# Hedgehog.net
KiCad netlist of a schematic drawn in Altium Designer
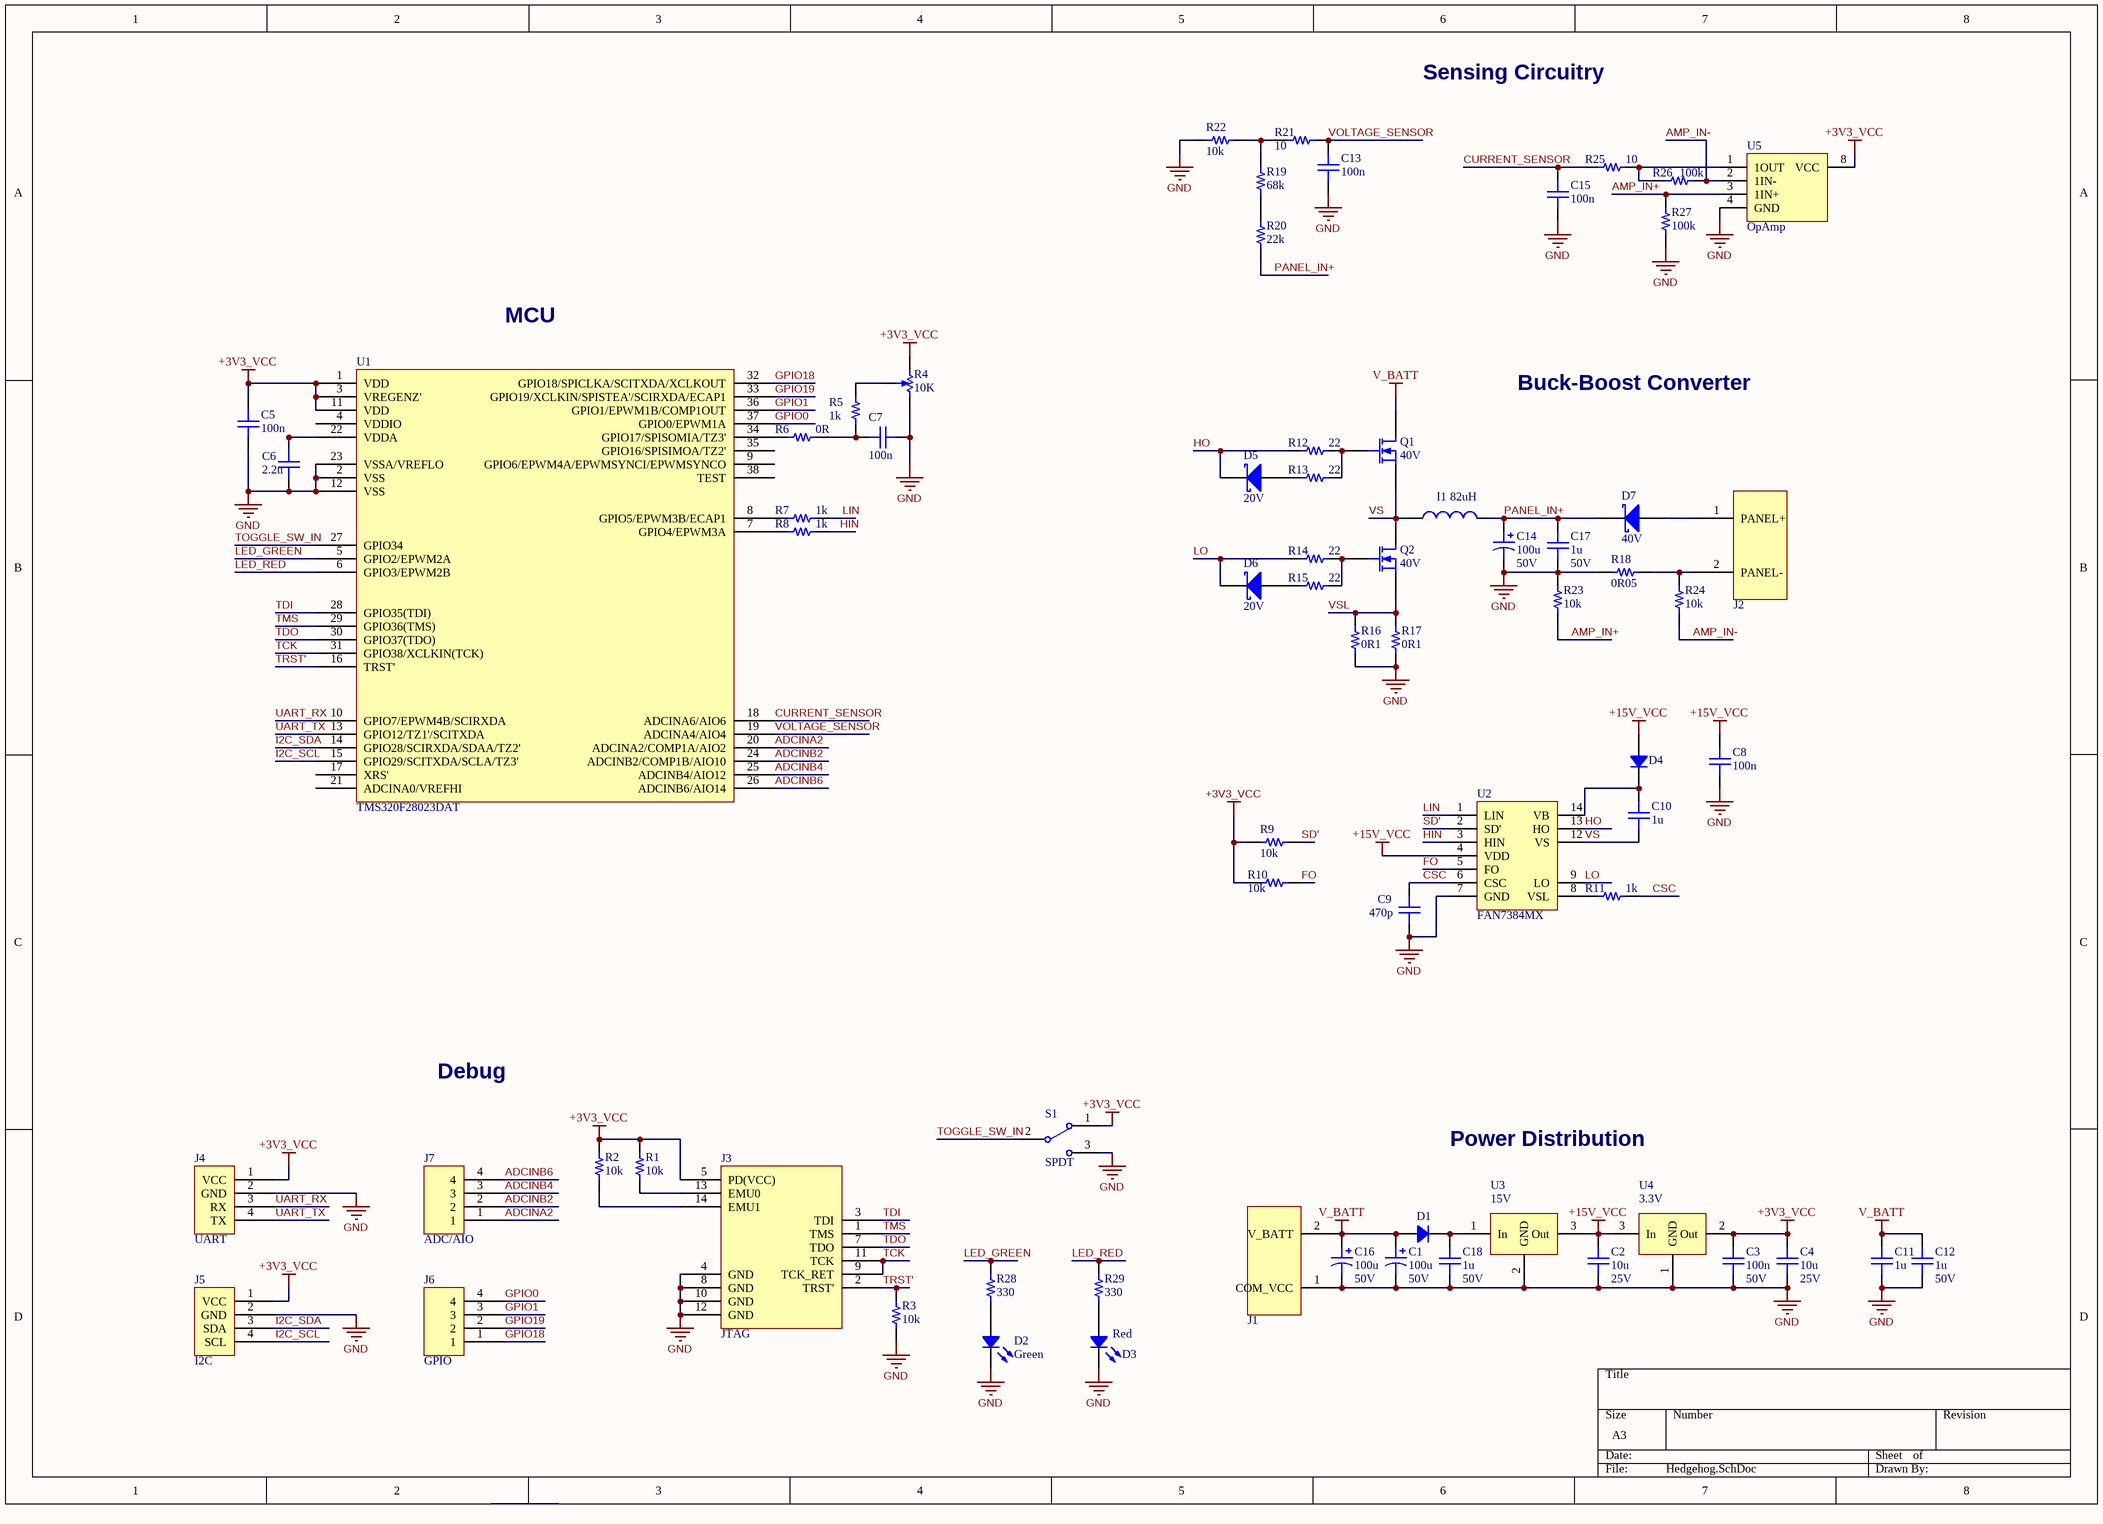
[diagram p0: Hedgehog.SchDoc]

(export (version "E")
  (design (tool "Eeschema 10.0.6"))
  (components
    (comp (ref "C1")
      (value "100u")
      (footprint "CAP-100uF-50V-20%-THM-Radial Panasonic Electronic Components")
      (description "Polarized Capacitor, 100uF, 50V Voltage Rating, Through Hole Radial Package")
      (fields (field (name "VOLTAGERATING") "50V"))
      (libsource (lib "PwrSupply-Schematics-Library") (part "100u-50V-THM-Radial-20%"))
    )
    (comp (ref "C2")
      (value "10u")
      (footprint "CAP 1206/3216 Murata")
      (description "Capacitor, 10uF, 25V Voltage Rating, 1206 Package")
      (fields (field (name "VOLTAGERATING") "25V"))
      (libsource (lib "Capacitor SMD") (part "10u-25V-1206-10%"))
    )
    (comp (ref "C3")
      (value "100n")
      (footprint "CAP 0805/2012")
      (description "Capacitor, 100nF, 50V Voltage Rating, 0805 Package")
      (fields (field (name "VOLTAGERATING") "50V"))
      (libsource (lib "Capacitor SMD") (part "100n-50V-0805-10%"))
    )
    (comp (ref "C4")
      (value "10u")
      (footprint "CAP 1206/3216 Murata")
      (description "Capacitor, 10uF, 25V Voltage Rating, 1206 Package")
      (fields (field (name "VOLTAGERATING") "25V"))
      (libsource (lib "Capacitor SMD") (part "10u-25V-1206-10%"))
    )
    (comp (ref "C5")
      (value "100n")
      (footprint "CAP 0805/2012")
      (description "Capacitor, 100nF, 50V Voltage Rating, 0805 Package")
      (libsource (lib "Capacitor SMD") (part "100n-50V-0805-10%"))
    )
    (comp (ref "C6")
      (value "2.2u")
      (footprint "CAP 0805/2012")
      (description "Capacitor, 2.2uF, 25V Voltage Rating, 0805 Package")
      (libsource (lib "Capacitor SMD") (part "2.2u-25V-0805-10%"))
    )
    (comp (ref "C7")
      (value "100n")
      (footprint "CAP 0805/2012")
      (description "Capacitor, 100nF, 50V Voltage Rating, 0805 Package")
      (libsource (lib "Capacitor SMD") (part "100n-50V-0805-10%"))
    )
    (comp (ref "C8")
      (value "100n")
      (footprint "CAP 0805/2012")
      (description "Capacitor, 100nF, 50V Voltage Rating, 0805 Package")
      (libsource (lib "Capacitor SMD") (part "100n-50V-0805-10%"))
    )
    (comp (ref "C9")
      (value "470p")
      (footprint "CAP 0805/2012")
      (description "Capacitor, 470pF, 50V Voltage Rating, 0805 Package")
      (libsource (lib "Capacitor SMD") (part "470p-50V-0805-5%"))
    )
    (comp (ref "C10")
      (value "1u")
      (footprint "CAP 0805/2012")
      (description "Capacitor,1uF, 25V Voltage Rating, 0805 Package")
      (libsource (lib "Capacitor SMD") (part "1u-25V-0805-10%"))
    )
    (comp (ref "C11")
      (value "1u")
      (footprint "CAP-TH-Radial_1uF-Non_Polarised-KEMET")
      (description "Capacitor, 1uF, 63V Voltage Rating, RADIAL Package")
      (libsource (lib "PwrSupply-Schematics-Library") (part "1u-63V-THM-Radial-10%"))
    )
    (comp (ref "C12")
      (value "1u")
      (footprint "CAP 1206/3216 Murata")
      (description "Capacitor, 1uF, 50V Voltage Rating, 1206 Package")
      (fields (field (name "VOLTAGERATING") "50V"))
      (libsource (lib "Capacitor SMD") (part "1u-50V-1206-10%"))
    )
    (comp (ref "C13")
      (value "100n")
      (footprint "CAP 0805/2012")
      (description "Capacitor, 100nF, 50V Voltage Rating, 0805 Package")
      (libsource (lib "Capacitor SMD") (part "100n-50V-0805-10%"))
    )
    (comp (ref "C14")
      (value "100u")
      (footprint "CAP-100uF-50V-20%-THM-Radial Panasonic Electronic Components")
      (description "Polarized Capacitor, 100uF, 50V Voltage Rating, Through Hole Radial Package")
      (fields (field (name "VOLTAGERATING") "50V"))
      (libsource (lib "PwrSupply-Schematics-Library") (part "100u-50V-THM-Radial-20%"))
    )
    (comp (ref "C15")
      (value "100n")
      (footprint "CAP 0805/2012")
      (description "Capacitor, 100nF, 50V Voltage Rating, 0805 Package")
      (libsource (lib "Capacitor SMD") (part "100n-50V-0805-10%"))
    )
    (comp (ref "C16")
      (value "100u")
      (footprint "CAP-100uF-50V-20%-THM-Radial Panasonic Electronic Components")
      (description "Polarized Capacitor, 100uF, 50V Voltage Rating, Through Hole Radial Package")
      (fields (field (name "VOLTAGERATING") "50V"))
      (libsource (lib "PwrSupply-Schematics-Library") (part "100u-50V-THM-Radial-20%"))
    )
    (comp (ref "C17")
      (value "1u")
      (footprint "CAP 1206/3216 Murata")
      (description "Capacitor, 1uF, 50V Voltage Rating, 1206 Package")
      (fields (field (name "VOLTAGERATING") "50V"))
      (libsource (lib "Capacitor SMD") (part "1u-50V-1206-10%"))
    )
    (comp (ref "C18")
      (value "1u")
      (footprint "CAP 1206/3216 Murata")
      (description "Capacitor, 1uF, 50V Voltage Rating, 1206 Package")
      (fields (field (name "VOLTAGERATING") "50V"))
      (libsource (lib "Capacitor SMD") (part "1u-50V-1206-10%"))
    )
    (comp (ref "D1")
      (value "400V-1A-GenPurp-SMA")
      (footprint "SMA Diodes Incorporated")
      (description "Diode, 400V Voltage Rating, 1A Current Rating, General Purpose Type, SMA Package")
      (fields (field (name "MANUFACTURER") "ON Semiconductor"))
      (libsource (lib "Diode SMD") (part "400V-1A-GenPurp-SMA"))
    )
    (comp (ref "D2")
      (value "LED-Green-1206")
      (footprint "LED 1206/3216 Kingbright")
      (description "LED, Green Color, 1206 Package")
      (fields (field (name "MANUFACTURER") "Kingbright") (field (name "COLOR") "Green"))
      (libsource (lib "Diode SMD") (part "LED-Green-1206"))
    )
    (comp (ref "D3")
      (value "LED-Red-1206")
      (footprint "LED 1206/3216 Kingbright")
      (description "LED, Red Color, 1206 Package")
      (fields (field (name "MANUFACTURER") "Kingbright") (field (name "COLOR") "Red"))
      (libsource (lib "Diode SMD") (part "LED-Red-1206"))
    )
    (comp (ref "D4")
      (value "400V-2A-Fast-SMA")
      (footprint "SMA Diodes Incorporated")
      (description "Diode, 400V Voltage Rating, 2A Current Rating, Fast Type, SMA Package")
      (fields (field (name "MANUFACTURER") "ON Semiconductor"))
      (libsource (lib "Diode SMD") (part "400V-2A-Fast-SMA"))
    )
    (comp (ref "D5")
      (value "20V-1A-SCHOTTKY-SOD123W")
      (footprint "CFP3-SOD123W-Nexperia USA Inc.")
      (description "Diode, 20V Voltage Rating, 1A Current Rating, SCHOTTKY Type, SOD123W Package")
      (fields (field (name "MANUFACTURER") "Nexperia USA Inc.") (field (name "VOLTAGERATING") "20V"))
      (libsource (lib "PwrSupply-Schematics-Library") (part "20V-1A-SCHOTTKY-SOD123W"))
    )
    (comp (ref "D6")
      (value "20V-1A-SCHOTTKY-SOD123W")
      (footprint "CFP3-SOD123W-Nexperia USA Inc.")
      (description "Diode, 20V Voltage Rating, 1A Current Rating, SCHOTTKY Type, SOD123W Package")
      (fields (field (name "MANUFACTURER") "Nexperia USA Inc.") (field (name "VOLTAGERATING") "20V"))
      (libsource (lib "PwrSupply-Schematics-Library") (part "20V-1A-SCHOTTKY-SOD123W"))
    )
    (comp (ref "D7")
      (value "40V-5A-SCHOTTKY-SMC")
      (footprint "DIOM6959X25L")
      (description "Diode, 40V Voltage Rating, 5A Current Rating, SCHOTTKY Type, SMC Package")
      (fields (field (name "MANUFACTURER") "Diodes Incorporated") (field (name "VOLTAGERATING") "40V"))
      (libsource (lib "PwrSupply-Schematics-Library") (part "40V-5A-SCHOTTKY-SMC"))
    )
    (comp (ref "I1")
      (value "82uH")
      (footprint "Inductor-82uH-Pulse Electronics Power")
      (description "82u, 6.5A Current Rating, 83mOhm Resistance, ThroughHole Package")
      (libsource (lib "PwrSupply-Schematics-Library") (part "82uH-6.5A-83mOhm"))
    )
    (comp (ref "J1")
      (value "~")
      (footprint "TWO_PIN_CONNECTOR-15A-On Shore Technology Inc.")
      (description "Slide Toggle Switch, 300V Voltage Rating, 15A Current Rating,")
      (fields (field (name "MANUFACTURER") "On Shore Technology Inc."))
      (libsource (lib "PwrSupply-Schematics-Library") (part "TwoPin-Connector-15A-300V-THM"))
    )
    (comp (ref "J2")
      (value "~")
      (footprint "TWO_PIN_CONNECTOR-15A-On Shore Technology Inc.")
      (description "Slide Toggle Switch, 300V Voltage Rating, 15A Current Rating,")
      (fields (field (name "MANUFACTURER") "On Shore Technology Inc."))
      (libsource (lib "") (part "TwoPin-Connector-15A-300V-THM_1"))
    )
    (comp (ref "J3")
      (value "JTAG")
      (footprint "14Pin-Connector-2.54mmx2.54mmPitch On Shore Technology Inc.")
      (description "14Pin-Connector")
      (fields (field (name "MANUFACTURER") "On Shore Technology Inc."))
      (libsource (lib "PwrSupply-Schematics-Library") (part "14Pin-Connector"))
    )
    (comp (ref "J4")
      (value "I2C")
      (footprint "4Pin_Connector-Wurth Electronics Inc.")
      (description "4Pin-Connector")
      (libsource (lib "PwrSupply-Schematics-Library") (part "4Pin-Connector"))
    )
    (comp (ref "J5")
      (value "UART")
      (footprint "4Pin_Connector-Wurth Electronics Inc.")
      (description "4Pin-Connector")
      (libsource (lib "PwrSupply-Schematics-Library") (part "4Pin-Connector"))
    )
    (comp (ref "J6")
      (value "GPIO")
      (footprint "4Pin_Connector-Wurth Electronics Inc.")
      (description "4Pin-Connector")
      (libsource (lib "") (part "4Pin-Connector_1"))
    )
    (comp (ref "J7")
      (value "ADC/AIO")
      (footprint "4Pin_Connector-Wurth Electronics Inc.")
      (description "4Pin-Connector")
      (libsource (lib "") (part "4Pin-Connector_1"))
    )
    (comp (ref "Q1")
      (value "40V")
      (footprint "DPAK/TO252-3-5.46mmWidth(Tab) ON Semiconductor - VIAS")
      (description "N-CH, 40V Voltage Rating, 6A Current Rating,  1.71W Power Rating, DPAK Package")
      (libsource (lib "PwrSupply-Schematics-Library") (part "Mosfet-40V-6A-1.71W-SMD-DPAK"))
    )
    (comp (ref "Q2")
      (value "40V")
      (footprint "DPAK/TO252-3-5.46mmWidth(Tab) ON Semiconductor - VIAS")
      (description "N-CH, 40V Voltage Rating, 6A Current Rating,  1.71W Power Rating, DPAK Package")
      (libsource (lib "PwrSupply-Schematics-Library") (part "Mosfet-40V-6A-1.71W-SMD-DPAK"))
    )
    (comp (ref "R1")
      (value "10k")
      (footprint "RES 0805/2012")
      (description "Resistor, 10k, 125mW Power Rating, 0805 Package")
      (libsource (lib "Resistor SMD") (part "10k-125mW-0805-1%"))
    )
    (comp (ref "R2")
      (value "10k")
      (footprint "RES 0805/2012")
      (description "Resistor, 10k, 125mW Power Rating, 0805 Package")
      (libsource (lib "Resistor SMD") (part "10k-125mW-0805-1%"))
    )
    (comp (ref "R3")
      (value "10k")
      (footprint "RES 0805/2012")
      (description "Resistor, 10k, 125mW Power Rating, 0805 Package")
      (libsource (lib "Resistor SMD") (part "10k-125mW-0805-1%"))
    )
    (comp (ref "R4")
      (value "10K")
      (footprint "Potentiometer-TC33X-2-103E-Bourns Inc.")
      (description "Potentiometer, 10kOhm Resistance, Current Rating, 0.1W Power Rating")
      (fields (field (name "MANUFACTURER") "Bourns Inc."))
      (libsource (lib "PwrSupply-Schematics-Library") (part "Pot-10kOhm-0.1W-20%"))
    )
    (comp (ref "R5")
      (value "1k")
      (footprint "RES 0805/2012")
      (description "Resistor, 1k, 125mW Power Rating, 0805 Package")
      (libsource (lib "Resistor SMD") (part "1k-125mW-0805-1%"))
    )
    (comp (ref "R6")
      (value "0R")
      (footprint "RES 0805/2012")
      (description "Resistor, 0 , 125mW Power Rating, 0805 Package")
      (libsource (lib "Resistor SMD") (part "0k-125mW-0805-Jumper"))
    )
    (comp (ref "R7")
      (value "1k")
      (footprint "RES 0805/2012")
      (description "Resistor, 1k, 125mW Power Rating, 0805 Package")
      (libsource (lib "Resistor SMD") (part "1k-125mW-0805-1%"))
    )
    (comp (ref "R8")
      (value "1k")
      (footprint "RES 0805/2012")
      (description "Resistor, 1k, 125mW Power Rating, 0805 Package")
      (libsource (lib "Resistor SMD") (part "1k-125mW-0805-1%"))
    )
    (comp (ref "R9")
      (value "10k")
      (footprint "RES 0805/2012")
      (description "Resistor, 10k, 125mW Power Rating, 0805 Package")
      (libsource (lib "Resistor SMD") (part "10k-125mW-0805-1%"))
    )
    (comp (ref "R10")
      (value "10k")
      (footprint "RES 0805/2012")
      (description "Resistor, 10k, 125mW Power Rating, 0805 Package")
      (libsource (lib "Resistor SMD") (part "10k-125mW-0805-1%"))
    )
    (comp (ref "R11")
      (value "1k")
      (footprint "RES 0805/2012")
      (description "Resistor, 1k, 125mW Power Rating, 0805 Package")
      (libsource (lib "Resistor SMD") (part "1k-125mW-0805-1%"))
    )
    (comp (ref "R12")
      (value "22")
      (footprint "RES 0805/2012")
      (description "Resistor, 22, 125mW Power Rating, 0805 Package")
      (libsource (lib "Resistor SMD") (part "22-125mW-0805-1%"))
    )
    (comp (ref "R13")
      (value "22")
      (footprint "RES 0805/2012")
      (description "Resistor, 22, 125mW Power Rating, 0805 Package")
      (libsource (lib "Resistor SMD") (part "22-125mW-0805-1%"))
    )
    (comp (ref "R14")
      (value "22")
      (footprint "RES 0805/2012")
      (description "Resistor, 22, 125mW Power Rating, 0805 Package")
      (libsource (lib "Resistor SMD") (part "22-125mW-0805-1%"))
    )
    (comp (ref "R15")
      (value "22")
      (footprint "RES 0805/2012")
      (description "Resistor, 22, 125mW Power Rating, 0805 Package")
      (libsource (lib "Resistor SMD") (part "22-125mW-0805-1%"))
    )
    (comp (ref "R16")
      (value "0R1")
      (footprint "RES 2512/6432")
      (description "Resistor, 0.1 Ohm, 1W Power Rating, 2010 Package")
      (libsource (lib "PwrSupply-Schematics-Library") (part "RES-0.1-1W-SMD-2010-1%"))
    )
    (comp (ref "R17")
      (value "0R1")
      (footprint "RES 2512/6432")
      (description "Resistor, 0.1 Ohm, 1W Power Rating, 2010 Package")
      (libsource (lib "PwrSupply-Schematics-Library") (part "RES-0.1-1W-SMD-2010-1%"))
    )
    (comp (ref "R18")
      (value "0R05")
      (footprint "RES 2512/6432")
      (description "Resistor, 0.05 Ohm, 3W Power Rating, 2512 Package")
      (libsource (lib "PwrSupply-Schematics-Library") (part "RES-0.05-3W-SMD-2512-1%"))
    )
    (comp (ref "R19")
      (value "68k")
      (footprint "RES 0805/2012")
      (description "Resistor, 68k, 125mW Power Rating, Package")
      (libsource (lib "Resistor SMD") (part "68k-125mW-0805-1%"))
    )
    (comp (ref "R20")
      (value "22k")
      (footprint "RES 0805/2012")
      (description "Resistor, 22k, 125mW Power Rating, 0805 Package")
      (libsource (lib "Resistor SMD") (part "22k-125mW-0805-1%"))
    )
    (comp (ref "R21")
      (value "10")
      (footprint "RES 0805/2012")
      (description "Resistor, 10, 125mW Power Rating, 0805 Package")
      (libsource (lib "Resistor SMD") (part "10-125mW-0805-1%"))
    )
    (comp (ref "R22")
      (value "10k")
      (footprint "RES 0805/2012")
      (description "Resistor, 10k, 125mW Power Rating, 0805 Package")
      (libsource (lib "Resistor SMD") (part "10k-125mW-0805-1%"))
    )
    (comp (ref "R23")
      (value "10k")
      (footprint "RES 0805/2012")
      (description "Resistor, 10k, 125mW Power Rating, 0805 Package")
      (libsource (lib "Resistor SMD") (part "10k-125mW-0805-1%"))
    )
    (comp (ref "R24")
      (value "10k")
      (footprint "RES 0805/2012")
      (description "Resistor, 10k, 125mW Power Rating, 0805 Package")
      (libsource (lib "Resistor SMD") (part "10k-125mW-0805-1%"))
    )
    (comp (ref "R25")
      (value "10")
      (footprint "RES 0805/2012")
      (description "Resistor, 10, 125mW Power Rating, 0805 Package")
      (libsource (lib "Resistor SMD") (part "10-125mW-0805-1%"))
    )
    (comp (ref "R26")
      (value "100k")
      (footprint "RES 0805/2012")
      (description "Resistor, 100k, 125mW Power Rating, 0805 Package")
      (libsource (lib "Resistor SMD") (part "100k-125mW-0805-1%"))
    )
    (comp (ref "R27")
      (value "100k")
      (footprint "RES 0805/2012")
      (description "Resistor, 100k, 125mW Power Rating, 0805 Package")
      (libsource (lib "Resistor SMD") (part "100k-125mW-0805-1%"))
    )
    (comp (ref "R28")
      (value "330")
      (footprint "RES 0805/2012")
      (description "Resistor, 330, 125mW Power Rating, 0805 Package")
      (libsource (lib "Resistor SMD") (part "330-125mW-0805-1%"))
    )
    (comp (ref "R29")
      (value "330")
      (footprint "RES 0805/2012")
      (description "Resistor, 330, 125mW Power Rating, 0805 Package")
      (libsource (lib "Resistor SMD") (part "330-125mW-0805-1%"))
    )
    (comp (ref "S1")
      (value "SPDT")
      (footprint "Toggle_Switch-SPDT-C&K")
      (description "Slide Toggle Switch, 12V Voltage Rating, 100mA Current Rating, Through Hole Package")
      (fields (field (name "MANUFACTURER") "C&K"))
      (libsource (lib "PwrSupply-Schematics-Library") (part "ToggleSwitch-SPDT-12V-100mA"))
    )
    (comp (ref "U1")
      (value "TMS320F28023DAT")
      (description "IC MCU 32BIT 64KB FLASH 38TSSOP")
      (fields (field (name "MANUFACTURER") "Texas Instruments"))
      (libsource (lib "PwrSupply-Schematics-Library") (part "MC-TMS320F28023DAT_Modified"))
    )
    (comp (ref "U2")
      (value "FAN7384MX")
      (footprint "14SOIC-3.9mmWidth ON Semiconductor")
      (description "Half-Bridge Gate Driver IC Non-Inverting 14-SOIC")
      (fields (field (name "MANUFACTURER") "ON Semiconductor"))
      (libsource (lib "IC Driver") (part "FAN7384MX"))
    )
    (comp (ref "U3")
      (value "15V")
      (footprint "DPAK/TO252-3-5.46mmWidth(Tab) ON Semiconductor")
      (description "Voltage Regulator, 15V OutputVoltage, 1A MaxCurrent, LDO Type, DPAK Package")
      (fields (field (name "MANUFACTURER") "ON Semiconductor") (field (name "OUTPUTVOLTAGE") "15V"))
      (libsource (lib "PwrSupply-Schematics-Library") (part "15V-1A-LDO-SMD-DPAK"))
    )
    (comp (ref "U4")
      (value "Voltage Regulator")
      (footprint "SOT223/TO261-4 Diodes Incorporated")
      (description "Voltage Regulator, 3.3V OutputVoltage, 1A MaxCurrent, LDO Type, SOT223 Package")
      (fields (field (name "MANUFACTURER") "Diodes Incorporated") (field (name "OUTPUTVOLTAGE") "3.3V"))
      (libsource (lib "IC Regulator") (part "3.3V-1A-LDO-SMD-SOT223_2"))
    )
    (comp (ref "U5")
      (value "OpAmp")
      (footprint "8SOIC-3.9mmWidth")
      (description "IC OPAMP GP 700KHZ 8SOIC")
      (fields (field (name "MANUFACTURER") "Texas Instruments"))
      (libsource (lib "IC OpAmp") (part "LM358AD"))
    )
  )
  (nets
    (net (code "1") (name "+3V3_VCC") (class "Default")
      (node (ref "C3") (pin "2") (pinfunction "2_2") (pintype "passive"))
      (node (ref "C4") (pin "1") (pinfunction "1_1") (pintype "passive"))
      (node (ref "C5") (pin "2") (pinfunction "2_2") (pintype "passive"))
      (node (ref "J3") (pin "5") (pinfunction "PD(VCC)_5") (pintype "passive"))
      (node (ref "J4") (pin "1") (pinfunction "VCC_1") (pintype "passive"))
      (node (ref "J5") (pin "1") (pinfunction "VCC_1") (pintype "passive"))
      (node (ref "R1") (pin "2") (pinfunction "2_2") (pintype "passive"))
      (node (ref "R10") (pin "1") (pinfunction "1_1") (pintype "passive"))
      (node (ref "R2") (pin "2") (pinfunction "2_2") (pintype "passive"))
      (node (ref "R4") (pin "3") (pinfunction "CW_3") (pintype "passive"))
      (node (ref "R9") (pin "1") (pinfunction "1_1") (pintype "passive"))
      (node (ref "S1") (pin "1") (pinfunction "3_1") (pintype "passive"))
      (node (ref "U1") (pin "1") (pinfunction "VDD_1") (pintype "passive"))
      (node (ref "U1") (pin "11") (pinfunction "VDD_11") (pintype "passive"))
      (node (ref "U1") (pin "3") (pinfunction "VREGENZ'_3") (pintype "passive"))
      (node (ref "U4") (pin "2") (pinfunction "Out_2") (pintype "passive"))
      (node (ref "U5") (pin "8") (pinfunction "VCC_8") (pintype "passive"))
    )
    (net (code "2") (name "+15V_VCC") (class "Default")
      (node (ref "C2") (pin "1") (pinfunction "1_1") (pintype "passive"))
      (node (ref "C8") (pin "1") (pinfunction "1_1") (pintype "passive"))
      (node (ref "D4") (pin "1") (pinfunction "1_1") (pintype "passive"))
      (node (ref "U2") (pin "4") (pinfunction "VDD_4") (pintype "passive"))
      (node (ref "U3") (pin "3") (pinfunction "Out_3") (pintype "passive"))
      (node (ref "U4") (pin "3") (pinfunction "In_3") (pintype "passive"))
    )
    (net (code "3") (name "/ADCINA2") (class "Default")
      (node (ref "J7") (pin "1") (pinfunction "1_1") (pintype "passive"))
      (node (ref "U1") (pin "20") (pinfunction "ADCINA2/COMP1A/AIO2_20") (pintype "passive"))
    )
    (net (code "4") (name "/ADCINB2") (class "Default")
      (node (ref "J7") (pin "2") (pinfunction "2_2") (pintype "passive"))
      (node (ref "U1") (pin "24") (pinfunction "ADCINB2/COMP1B/AIO10_24") (pintype "passive"))
    )
    (net (code "5") (name "/ADCINB4") (class "Default")
      (node (ref "J7") (pin "3") (pinfunction "3_3") (pintype "passive"))
      (node (ref "U1") (pin "25") (pinfunction "ADCINB4/AIO12_25") (pintype "passive"))
    )
    (net (code "6") (name "/ADCINB6") (class "Default")
      (node (ref "J7") (pin "4") (pinfunction "4_4") (pintype "passive"))
      (node (ref "U1") (pin "26") (pinfunction "ADCINB6/AIO14_26") (pintype "passive"))
    )
    (net (code "7") (name "/AMP_IN+") (class "Default")
      (node (ref "R23") (pin "1") (pinfunction "1_1") (pintype "passive"))
      (node (ref "R27") (pin "1") (pinfunction "1_1") (pintype "passive"))
      (node (ref "U5") (pin "3") (pinfunction "1IN+_3") (pintype "passive"))
    )
    (net (code "8") (name "/AMP_IN-") (class "Default")
      (node (ref "R24") (pin "1") (pinfunction "1_1") (pintype "passive"))
      (node (ref "R26") (pin "2") (pinfunction "2_2") (pintype "passive"))
      (node (ref "U5") (pin "2") (pinfunction "1IN-_2") (pintype "passive"))
    )
    (net (code "9") (name "/CSC") (class "Default")
      (node (ref "C9") (pin "2") (pinfunction "2_2") (pintype "passive"))
      (node (ref "R11") (pin "1") (pinfunction "1_1") (pintype "passive"))
      (node (ref "U2") (pin "6") (pinfunction "CSC_6") (pintype "passive"))
    )
    (net (code "10") (name "/CURRENT_SENSOR") (class "Default")
      (node (ref "C15") (pin "1") (pinfunction "1_1") (pintype "passive"))
      (node (ref "R25") (pin "2") (pinfunction "2_2") (pintype "passive"))
      (node (ref "U1") (pin "18") (pinfunction "ADCINA6/AIO6_18") (pintype "passive"))
    )
    (net (code "11") (name "/FO") (class "Default")
      (node (ref "R10") (pin "2") (pinfunction "2_2") (pintype "passive"))
      (node (ref "U2") (pin "5") (pinfunction "FO_5") (pintype "passive"))
    )
    (net (code "12") (name "/GPIO0") (class "Default")
      (node (ref "J6") (pin "4") (pinfunction "4_4") (pintype "passive"))
      (node (ref "U1") (pin "37") (pinfunction "GPIO0/EPWM1A_37") (pintype "passive"))
    )
    (net (code "13") (name "/GPIO1") (class "Default")
      (node (ref "J6") (pin "3") (pinfunction "3_3") (pintype "passive"))
      (node (ref "U1") (pin "36") (pinfunction "GPIO1/EPWM1B/COMP1OUT_36") (pintype "passive"))
    )
    (net (code "14") (name "/GPIO18") (class "Default")
      (node (ref "J6") (pin "1") (pinfunction "1_1") (pintype "passive"))
      (node (ref "U1") (pin "32") (pinfunction "GPIO18/SPICLKA/SCITXDA/XCLKOUT_32") (pintype "passive"))
    )
    (net (code "15") (name "/GPIO19") (class "Default")
      (node (ref "J6") (pin "2") (pinfunction "2_2") (pintype "passive"))
      (node (ref "U1") (pin "33") (pinfunction "GPIO19/XCLKIN/SPISTEA'/SCIRXDA/ECAP1_33") (pintype "passive"))
    )
    (net (code "16") (name "/HIN") (class "Default")
      (node (ref "R8") (pin "2") (pinfunction "2_2") (pintype "passive"))
      (node (ref "U2") (pin "3") (pinfunction "HIN_3") (pintype "passive"))
    )
    (net (code "17") (name "/HO") (class "Default")
      (node (ref "D5") (pin "2") (pinfunction "K_2") (pintype "passive"))
      (node (ref "R12") (pin "1") (pinfunction "1_1") (pintype "passive"))
      (node (ref "U2") (pin "13") (pinfunction "HO_13") (pintype "passive"))
    )
    (net (code "18") (name "/I2C_SCL") (class "Default")
      (node (ref "J5") (pin "4") (pinfunction "SCL_4") (pintype "passive"))
      (node (ref "U1") (pin "15") (pinfunction "GPIO29/SCITXDA/SCLA/TZ3'_15") (pintype "passive"))
    )
    (net (code "19") (name "/I2C_SDA") (class "Default")
      (node (ref "J5") (pin "3") (pinfunction "SDA_3") (pintype "passive"))
      (node (ref "U1") (pin "14") (pinfunction "GPIO28/SCIRXDA/SDAA/TZ2'_14") (pintype "passive"))
    )
    (net (code "20") (name "/LED_GREEN") (class "Default")
      (node (ref "R28") (pin "2") (pinfunction "2_2") (pintype "passive"))
      (node (ref "U1") (pin "5") (pinfunction "GPIO2/EPWM2A_5") (pintype "passive"))
    )
    (net (code "21") (name "/LED_RED") (class "Default")
      (node (ref "R29") (pin "2") (pinfunction "2_2") (pintype "passive"))
      (node (ref "U1") (pin "6") (pinfunction "GPIO3/EPWM2B_6") (pintype "passive"))
    )
    (net (code "22") (name "/LIN") (class "Default")
      (node (ref "R7") (pin "2") (pinfunction "2_2") (pintype "passive"))
      (node (ref "U2") (pin "1") (pinfunction "LIN_1") (pintype "passive"))
    )
    (net (code "23") (name "/LO") (class "Default")
      (node (ref "D6") (pin "2") (pinfunction "K_2") (pintype "passive"))
      (node (ref "R14") (pin "1") (pinfunction "1_1") (pintype "passive"))
      (node (ref "U2") (pin "9") (pinfunction "LO_9") (pintype "passive"))
    )
    (net (code "24") (name "/PANEL_IN+") (class "Default")
      (node (ref "C14") (pin "1") (pinfunction "1_1") (pintype "passive"))
      (node (ref "C17") (pin "2") (pinfunction "2_2") (pintype "passive"))
      (node (ref "D7") (pin "2") (pinfunction "K_2") (pintype "passive"))
      (node (ref "I1") (pin "2") (pinfunction "2_2") (pintype "passive"))
      (node (ref "R20") (pin "1") (pinfunction "1_1") (pintype "passive"))
    )
    (net (code "25") (name "/SD'") (class "Default")
      (node (ref "R9") (pin "2") (pinfunction "2_2") (pintype "passive"))
      (node (ref "U2") (pin "2") (pinfunction "SD'_2") (pintype "passive"))
    )
    (net (code "26") (name "/TCK") (class "Default")
      (node (ref "J3") (pin "11") (pinfunction "TCK_11") (pintype "passive"))
      (node (ref "J3") (pin "9") (pinfunction "TCK_RET_9") (pintype "passive"))
      (node (ref "U1") (pin "31") (pinfunction "GPIO38/XCLKIN(TCK)_31") (pintype "passive"))
    )
    (net (code "27") (name "/TDI") (class "Default")
      (node (ref "J3") (pin "3") (pinfunction "TDI_3") (pintype "passive"))
      (node (ref "U1") (pin "28") (pinfunction "GPIO35(TDI)_28") (pintype "passive"))
    )
    (net (code "28") (name "/TDO") (class "Default")
      (node (ref "J3") (pin "7") (pinfunction "TDO_7") (pintype "passive"))
      (node (ref "U1") (pin "30") (pinfunction "GPIO37(TDO)_30") (pintype "passive"))
    )
    (net (code "29") (name "/TMS") (class "Default")
      (node (ref "J3") (pin "1") (pinfunction "TMS_1") (pintype "passive"))
      (node (ref "U1") (pin "29") (pinfunction "GPIO36(TMS)_29") (pintype "passive"))
    )
    (net (code "30") (name "/TOGGLE_SW_IN") (class "Default")
      (node (ref "S1") (pin "2") (pinfunction "2_2") (pintype "passive"))
      (node (ref "U1") (pin "27") (pinfunction "GPIO34_27") (pintype "passive"))
    )
    (net (code "31") (name "/TRST'") (class "Default")
      (node (ref "J3") (pin "2") (pinfunction "TRST'_2") (pintype "passive"))
      (node (ref "R3") (pin "2") (pinfunction "2_2") (pintype "passive"))
      (node (ref "U1") (pin "16") (pinfunction "TRST'_16") (pintype "passive"))
    )
    (net (code "32") (name "/UART_RX") (class "Default")
      (node (ref "J4") (pin "3") (pinfunction "SDA_3") (pintype "passive"))
      (node (ref "U1") (pin "10") (pinfunction "GPIO7/EPWM4B/SCIRXDA_10") (pintype "passive"))
    )
    (net (code "33") (name "/UART_TX") (class "Default")
      (node (ref "J4") (pin "4") (pinfunction "SCL_4") (pintype "passive"))
      (node (ref "U1") (pin "13") (pinfunction "GPIO12/TZ1'/SCITXDA_13") (pintype "passive"))
    )
    (net (code "34") (name "/VOLTAGE_SENSOR") (class "Default")
      (node (ref "C13") (pin "2") (pinfunction "2_2") (pintype "passive"))
      (node (ref "R21") (pin "2") (pinfunction "2_2") (pintype "passive"))
      (node (ref "U1") (pin "19") (pinfunction "ADCINA4/AIO4_19") (pintype "passive"))
    )
    (net (code "35") (name "/VS") (class "Default")
      (node (ref "C10") (pin "1") (pinfunction "1_1") (pintype "passive"))
      (node (ref "I1") (pin "1") (pinfunction "1_1") (pintype "passive"))
      (node (ref "Q1") (pin "3") (pinfunction "S_3") (pintype "passive"))
      (node (ref "Q2") (pin "2") (pinfunction "D_2") (pintype "passive"))
      (node (ref "U2") (pin "12") (pinfunction "VS_12") (pintype "passive"))
    )
    (net (code "36") (name "/VSL") (class "Default")
      (node (ref "Q2") (pin "3") (pinfunction "S_3") (pintype "passive"))
      (node (ref "R16") (pin "2") (pinfunction "2_2") (pintype "passive"))
      (node (ref "R17") (pin "2") (pinfunction "2_2") (pintype "passive"))
    )
    (net (code "37") (name "GND") (class "Default")
      (node (ref "C1") (pin "2") (pinfunction "2_2") (pintype "passive"))
      (node (ref "C11") (pin "1") (pinfunction "1_1") (pintype "passive"))
      (node (ref "C12") (pin "1") (pinfunction "1_1") (pintype "passive"))
      (node (ref "C13") (pin "1") (pinfunction "1_1") (pintype "passive"))
      (node (ref "C14") (pin "2") (pinfunction "2_2") (pintype "passive"))
      (node (ref "C15") (pin "2") (pinfunction "2_2") (pintype "passive"))
      (node (ref "C16") (pin "2") (pinfunction "2_2") (pintype "passive"))
      (node (ref "C17") (pin "1") (pinfunction "1_1") (pintype "passive"))
      (node (ref "C18") (pin "1") (pinfunction "1_1") (pintype "passive"))
      (node (ref "C2") (pin "2") (pinfunction "2_2") (pintype "passive"))
      (node (ref "C3") (pin "1") (pinfunction "1_1") (pintype "passive"))
      (node (ref "C4") (pin "2") (pinfunction "2_2") (pintype "passive"))
      (node (ref "C5") (pin "1") (pinfunction "1_1") (pintype "passive"))
      (node (ref "C6") (pin "1") (pinfunction "1_1") (pintype "passive"))
      (node (ref "C7") (pin "1") (pinfunction "1_1") (pintype "passive"))
      (node (ref "C8") (pin "2") (pinfunction "2_2") (pintype "passive"))
      (node (ref "C9") (pin "1") (pinfunction "1_1") (pintype "passive"))
      (node (ref "D2") (pin "2") (pinfunction "2_2") (pintype "passive"))
      (node (ref "D3") (pin "2") (pinfunction "2_2") (pintype "passive"))
      (node (ref "J1") (pin "1") (pinfunction "COM_VCC_1") (pintype "passive"))
      (node (ref "J3") (pin "10") (pinfunction "GND_10") (pintype "passive"))
      (node (ref "J3") (pin "12") (pinfunction "GND_12") (pintype "passive"))
      (node (ref "J3") (pin "4") (pinfunction "GND_4") (pintype "passive"))
      (node (ref "J3") (pin "8") (pinfunction "GND_8") (pintype "passive"))
      (node (ref "J4") (pin "2") (pinfunction "GND_2") (pintype "passive"))
      (node (ref "J5") (pin "2") (pinfunction "GND_2") (pintype "passive"))
      (node (ref "R16") (pin "1") (pinfunction "1_1") (pintype "passive"))
      (node (ref "R17") (pin "1") (pinfunction "1_1") (pintype "passive"))
      (node (ref "R18") (pin "1") (pinfunction "1_1") (pintype "passive"))
      (node (ref "R22") (pin "2") (pinfunction "2_2") (pintype "passive"))
      (node (ref "R23") (pin "2") (pinfunction "2_2") (pintype "passive"))
      (node (ref "R27") (pin "2") (pinfunction "2_2") (pintype "passive"))
      (node (ref "R3") (pin "1") (pinfunction "1_1") (pintype "passive"))
      (node (ref "R4") (pin "1") (pinfunction "CCW_1") (pintype "passive"))
      (node (ref "S1") (pin "3") (pinfunction "1_3") (pintype "passive"))
      (node (ref "U1") (pin "12") (pinfunction "VSS_12") (pintype "passive"))
      (node (ref "U1") (pin "2") (pinfunction "VSS_2") (pintype "passive"))
      (node (ref "U1") (pin "23") (pinfunction "VSSA/VREFLO_23") (pintype "passive"))
      (node (ref "U2") (pin "7") (pinfunction "GND_7") (pintype "passive"))
      (node (ref "U3") (pin "2") (pinfunction "GND_2") (pintype "passive"))
      (node (ref "U4") (pin "1") (pinfunction "GND_1") (pintype "passive"))
      (node (ref "U5") (pin "4") (pinfunction "GND_4") (pintype "passive"))
    )
    (net (code "38") (name "Net-(C7-Pad2)") (class "Default")
      (node (ref "C7") (pin "2") (pinfunction "2_2") (pintype "passive"))
      (node (ref "R5") (pin "1") (pinfunction "1_1") (pintype "passive"))
      (node (ref "R6") (pin "2") (pinfunction "2_2") (pintype "passive"))
    )
    (net (code "39") (name "Net-(D2-Pad1)") (class "Default")
      (node (ref "D2") (pin "1") (pinfunction "1_1") (pintype "passive"))
      (node (ref "R28") (pin "1") (pinfunction "1_1") (pintype "passive"))
    )
    (net (code "40") (name "Net-(D3-Pad1)") (class "Default")
      (node (ref "D3") (pin "1") (pinfunction "1_1") (pintype "passive"))
      (node (ref "R29") (pin "1") (pinfunction "1_1") (pintype "passive"))
    )
    (net (code "41") (name "Net-(D5-A)") (class "Default")
      (node (ref "D5") (pin "1") (pinfunction "A_1") (pintype "passive"))
      (node (ref "R13") (pin "1") (pinfunction "1_1") (pintype "passive"))
    )
    (net (code "42") (name "Net-(D6-A)") (class "Default")
      (node (ref "D6") (pin "1") (pinfunction "A_1") (pintype "passive"))
      (node (ref "R15") (pin "1") (pinfunction "1_1") (pintype "passive"))
    )
    (net (code "43") (name "Net-(D7-A)") (class "Default")
      (node (ref "D7") (pin "1") (pinfunction "A_1") (pintype "passive"))
      (node (ref "J2") (pin "1") (pinfunction "PANEL+_1") (pintype "passive"))
    )
    (net (code "44") (name "Net-(J2-PANEL-)") (class "Default")
      (node (ref "J2") (pin "2") (pinfunction "PANEL-_2") (pintype "passive"))
      (node (ref "R18") (pin "2") (pinfunction "2_2") (pintype "passive"))
      (node (ref "R24") (pin "2") (pinfunction "2_2") (pintype "passive"))
    )
    (net (code "45") (name "Net-(J3-EMU0)") (class "Default")
      (node (ref "J3") (pin "13") (pinfunction "EMU0_13") (pintype "passive"))
      (node (ref "R1") (pin "1") (pinfunction "1_1") (pintype "passive"))
    )
    (net (code "46") (name "Net-(J3-EMU1)") (class "Default")
      (node (ref "J3") (pin "14") (pinfunction "EMU1_14") (pintype "passive"))
      (node (ref "R2") (pin "1") (pinfunction "1_1") (pintype "passive"))
    )
    (net (code "47") (name "Net-(Q1-G)") (class "Default")
      (node (ref "Q1") (pin "1") (pinfunction "G_1") (pintype "passive"))
      (node (ref "R12") (pin "2") (pinfunction "2_2") (pintype "passive"))
      (node (ref "R13") (pin "2") (pinfunction "2_2") (pintype "passive"))
    )
    (net (code "48") (name "Net-(Q2-G)") (class "Default")
      (node (ref "Q2") (pin "1") (pinfunction "G_1") (pintype "passive"))
      (node (ref "R14") (pin "2") (pinfunction "2_2") (pintype "passive"))
      (node (ref "R15") (pin "2") (pinfunction "2_2") (pintype "passive"))
    )
    (net (code "49") (name "Net-(R4-W)") (class "Default")
      (node (ref "R4") (pin "2") (pinfunction "W_2") (pintype "passive"))
      (node (ref "R5") (pin "2") (pinfunction "2_2") (pintype "passive"))
    )
    (net (code "50") (name "Net-(R19-Pad1)") (class "Default")
      (node (ref "R19") (pin "1") (pinfunction "1_1") (pintype "passive"))
      (node (ref "R20") (pin "2") (pinfunction "2_2") (pintype "passive"))
    )
    (net (code "51") (name "Net-(R19-Pad2)") (class "Default")
      (node (ref "R19") (pin "2") (pinfunction "2_2") (pintype "passive"))
      (node (ref "R21") (pin "1") (pinfunction "1_1") (pintype "passive"))
      (node (ref "R22") (pin "1") (pinfunction "1_1") (pintype "passive"))
    )
    (net (code "52") (name "Net-(U1-GPIO4{slash}EPWM3A)") (class "Default")
      (node (ref "R8") (pin "1") (pinfunction "1_1") (pintype "passive"))
      (node (ref "U1") (pin "7") (pinfunction "GPIO4/EPWM3A_7") (pintype "passive"))
    )
    (net (code "53") (name "Net-(U1-GPIO5{slash}EPWM3B{slash}ECAP1)") (class "Default")
      (node (ref "R7") (pin "1") (pinfunction "1_1") (pintype "passive"))
      (node (ref "U1") (pin "8") (pinfunction "GPIO5/EPWM3B/ECAP1_8") (pintype "passive"))
    )
    (net (code "54") (name "Net-(U1-GPIO17{slash}SPISOMIA{slash}TZ3')") (class "Default")
      (node (ref "R6") (pin "1") (pinfunction "1_1") (pintype "passive"))
      (node (ref "U1") (pin "34") (pinfunction "GPIO17/SPISOMIA/TZ3'_34") (pintype "passive"))
    )
    (net (code "55") (name "Net-(U1-VDDA)") (class "Default")
      (node (ref "C6") (pin "2") (pinfunction "2_2") (pintype "passive"))
      (node (ref "U1") (pin "22") (pinfunction "VDDA_22") (pintype "passive"))
    )
    (net (code "56") (name "Net-(U2-VB)") (class "Default")
      (node (ref "C10") (pin "2") (pinfunction "2_2") (pintype "passive"))
      (node (ref "D4") (pin "2") (pinfunction "2_2") (pintype "passive"))
      (node (ref "U2") (pin "14") (pinfunction "VB_14") (pintype "passive"))
    )
    (net (code "57") (name "Net-(U2-VSL)") (class "Default")
      (node (ref "R11") (pin "2") (pinfunction "2_2") (pintype "passive"))
      (node (ref "U2") (pin "8") (pinfunction "VSL_8") (pintype "passive"))
    )
    (net (code "58") (name "Net-(U3-In)") (class "Default")
      (node (ref "C18") (pin "2") (pinfunction "2_2") (pintype "passive"))
      (node (ref "D1") (pin "2") (pinfunction "2_2") (pintype "passive"))
      (node (ref "U3") (pin "1") (pinfunction "In_1") (pintype "passive"))
    )
    (net (code "59") (name "Net-(U5-1OUT)") (class "Default")
      (node (ref "R25") (pin "1") (pinfunction "1_1") (pintype "passive"))
      (node (ref "R26") (pin "1") (pinfunction "1_1") (pintype "passive"))
      (node (ref "U5") (pin "1") (pinfunction "1OUT_1") (pintype "passive"))
    )
    (net (code "60") (name "V_BATT") (class "Default")
      (node (ref "C1") (pin "1") (pinfunction "1_1") (pintype "passive"))
      (node (ref "C11") (pin "2") (pinfunction "2_2") (pintype "passive"))
      (node (ref "C12") (pin "2") (pinfunction "2_2") (pintype "passive"))
      (node (ref "C16") (pin "1") (pinfunction "1_1") (pintype "passive"))
      (node (ref "D1") (pin "1") (pinfunction "1_1") (pintype "passive"))
      (node (ref "J1") (pin "2") (pinfunction "V_BATT_2") (pintype "passive"))
      (node (ref "Q1") (pin "2") (pinfunction "D_2") (pintype "passive"))
    )
    (net (code "61") (name "unconnected-(J3-N{slash}C-Pad6)") (class "Default")
      (node (ref "J3") (pin "6") (pinfunction "N/C_6") (pintype "passive"))
    )
    (net (code "62") (name "unconnected-(U1-ADCINA0{slash}VREFHI-Pad21)") (class "Default")
      (node (ref "U1") (pin "21") (pinfunction "ADCINA0/VREFHI_21") (pintype "passive"))
    )
    (net (code "63") (name "unconnected-(U1-GPIO6{slash}EPWM4A{slash}EPWMSYNCI{slash}EPWMSYNCO-Pad9)") (class "Default")
      (node (ref "U1") (pin "9") (pinfunction "GPIO6/EPWM4A/EPWMSYNCI/EPWMSYNCO_9") (pintype "passive"))
    )
    (net (code "64") (name "unconnected-(U1-GPIO16{slash}SPISIMOA{slash}TZ2'-Pad35)") (class "Default")
      (node (ref "U1") (pin "35") (pinfunction "GPIO16/SPISIMOA/TZ2'_35") (pintype "passive"))
    )
    (net (code "65") (name "unconnected-(U1-TEST-Pad38)") (class "Default")
      (node (ref "U1") (pin "38") (pinfunction "TEST_38") (pintype "passive"))
    )
    (net (code "66") (name "unconnected-(U1-VDDIO-Pad4)") (class "Default")
      (node (ref "U1") (pin "4") (pinfunction "VDDIO_4") (pintype "passive"))
    )
    (net (code "67") (name "unconnected-(U1-XRS'-Pad17)") (class "Default")
      (node (ref "U1") (pin "17") (pinfunction "XRS'_17") (pintype "passive"))
    )
    (net (code "68") (name "unconnected-(U2-NC-Pad10)") (class "Default")
      (node (ref "U2") (pin "10") (pinfunction "NC_10") (pintype "passive"))
    )
    (net (code "69") (name "unconnected-(U2-NC-Pad11)") (class "Default")
      (node (ref "U2") (pin "11") (pinfunction "NC_11") (pintype "passive"))
    )
    (net (code "70") (name "unconnected-(U5-2IN+-Pad5)") (class "Default")
      (node (ref "U5") (pin "5") (pinfunction "2IN+_5") (pintype "passive"))
    )
    (net (code "71") (name "unconnected-(U5-2IN--Pad6)") (class "Default")
      (node (ref "U5") (pin "6") (pinfunction "2IN-_6") (pintype "passive"))
    )
    (net (code "72") (name "unconnected-(U5-2OUT-Pad7)") (class "Default")
      (node (ref "U5") (pin "7") (pinfunction "2OUT_7") (pintype "passive"))
    )
  )
)
